# MAX31865_Layout_with_OLED.net
KiCad netlist of a schematic drawn in EAGLE
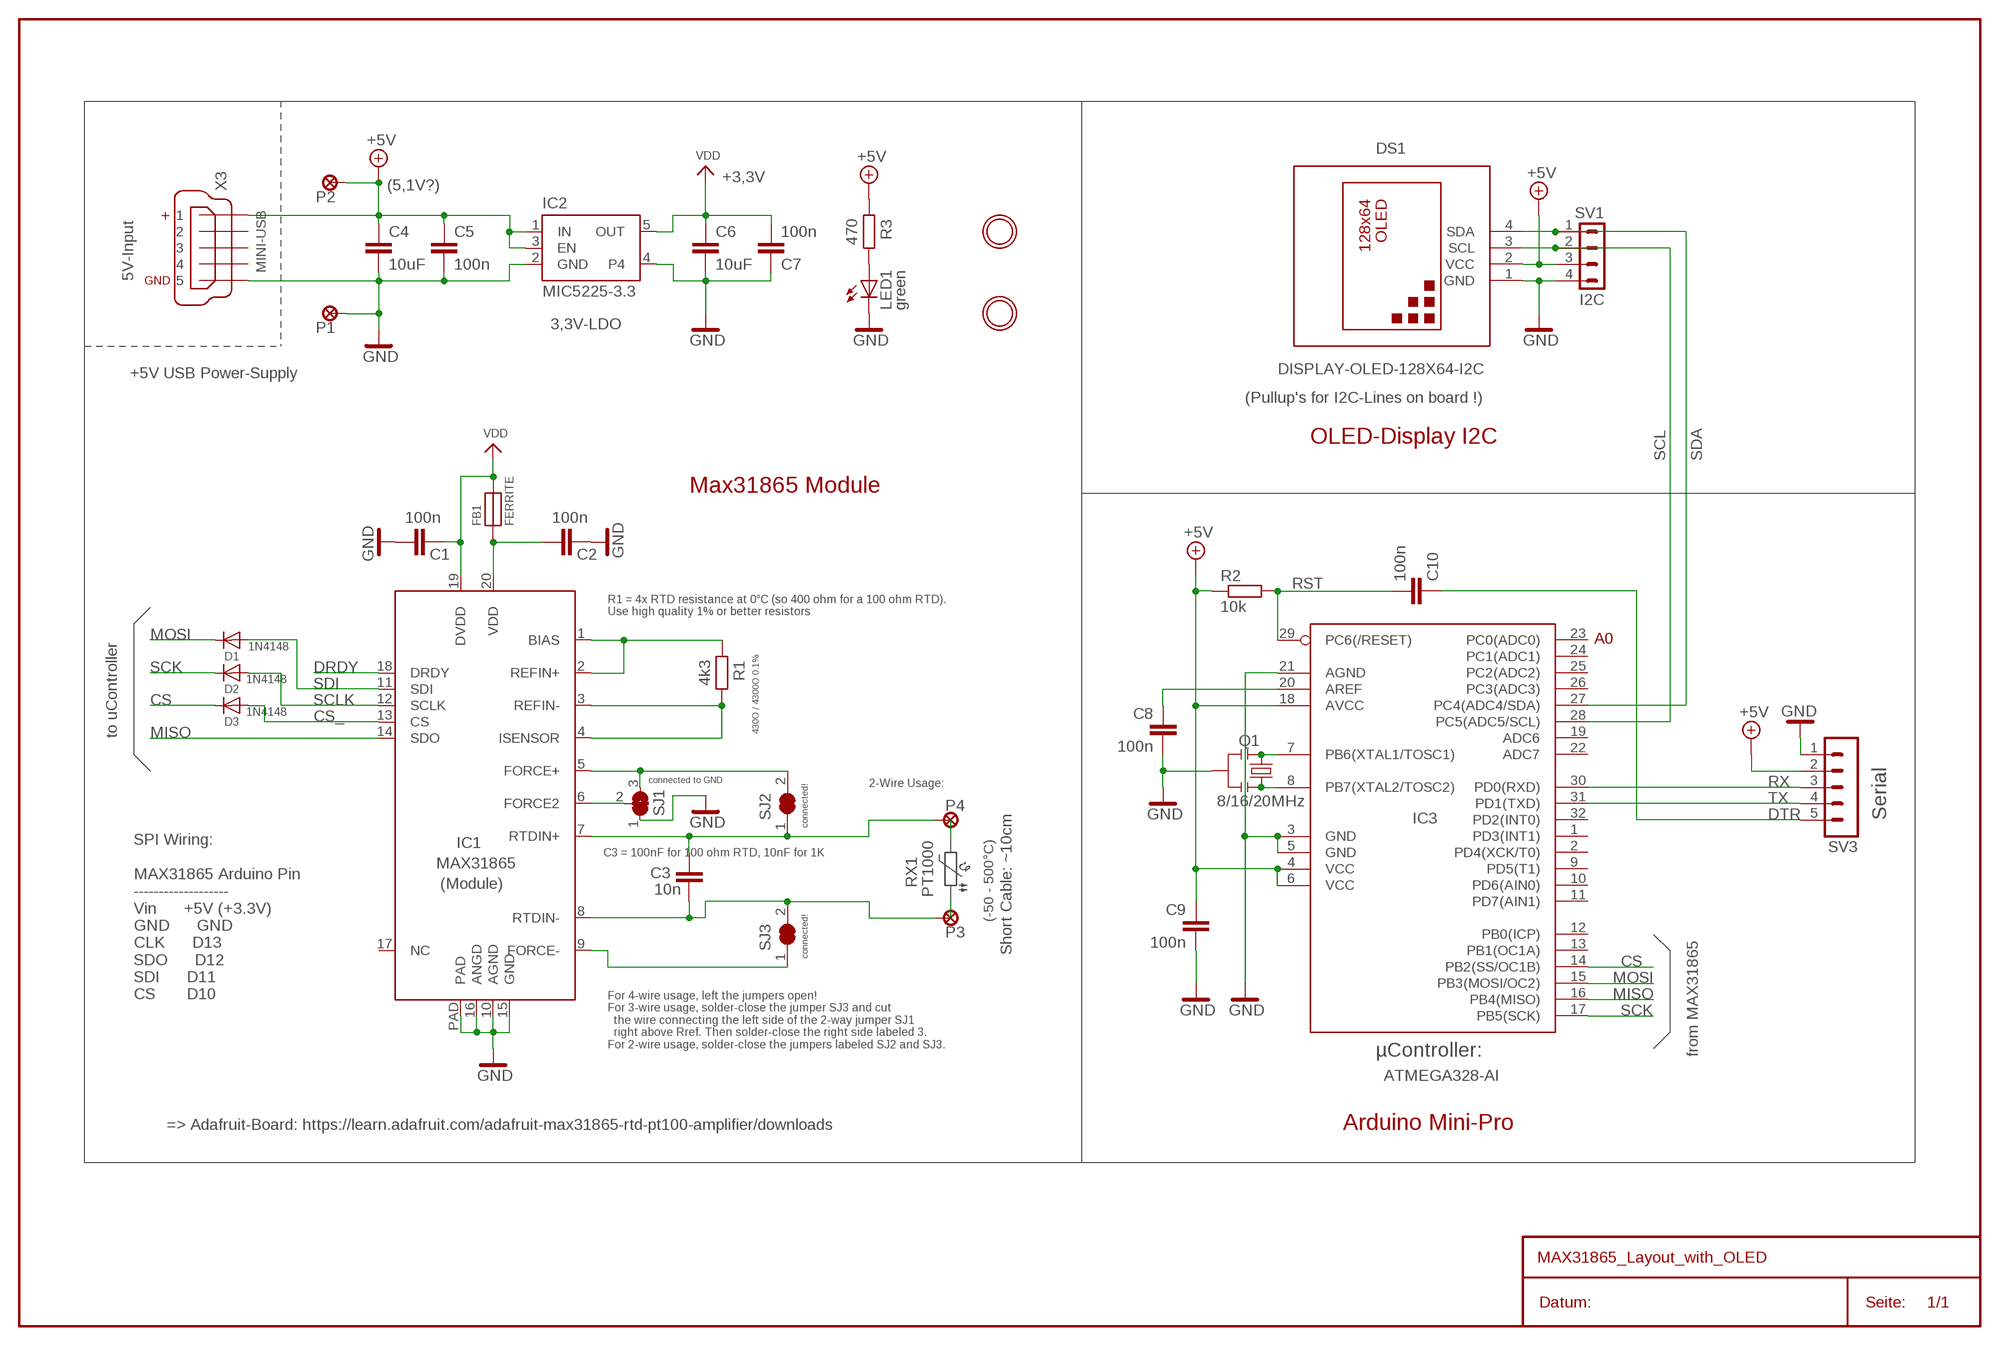
[diagram p0: schematic, sheet 1]

(export (version "E")
  (design (tool "Eeschema 10.0.6"))
  (components
    (comp (ref "C1")
      (value "100n")
      (footprint "eagle-import:C0603")
      (libsource (lib "eagle-import") (part "C-EUC0603"))
    )
    (comp (ref "C2")
      (value "100n")
      (footprint "eagle-import:C0603")
      (libsource (lib "eagle-import") (part "C-EUC0603"))
    )
    (comp (ref "C3")
      (value "10n")
      (footprint "eagle-import:C0603")
      (libsource (lib "eagle-import") (part "C-EUC0603"))
    )
    (comp (ref "C4")
      (value "10uF")
      (footprint "eagle-import:C0805")
      (libsource (lib "eagle-import") (part "C-EUC0805"))
    )
    (comp (ref "C5")
      (value "100n")
      (footprint "eagle-import:C0603")
      (libsource (lib "eagle-import") (part "C-EUC0603"))
    )
    (comp (ref "C6")
      (value "10uF")
      (footprint "eagle-import:C0603")
      (libsource (lib "eagle-import") (part "C-EUC0603"))
    )
    (comp (ref "C7")
      (value "100n")
      (footprint "eagle-import:C0603")
      (libsource (lib "eagle-import") (part "C-EUC0603"))
    )
    (comp (ref "C8")
      (value "100n")
      (footprint "eagle-import:C0603")
      (libsource (lib "eagle-import") (part "C-EUC0603"))
    )
    (comp (ref "C9")
      (value "100n")
      (footprint "eagle-import:C0603")
      (libsource (lib "eagle-import") (part "C-EUC0603"))
    )
    (comp (ref "C10")
      (value "100n")
      (footprint "eagle-import:C0603")
      (libsource (lib "eagle-import") (part "C-EUC0603"))
    )
    (comp (ref "D1")
      (value "1N4148")
      (footprint "eagle-import:SOD-323")
      (libsource (lib "eagle-import") (part "DIODESOD-323"))
    )
    (comp (ref "D2")
      (value "1N4148")
      (footprint "eagle-import:SOD-323")
      (libsource (lib "eagle-import") (part "DIODESOD-323"))
    )
    (comp (ref "D3")
      (value "1N4148")
      (footprint "eagle-import:SOD-323")
      (libsource (lib "eagle-import") (part "DIODESOD-323"))
    )
    (comp (ref "DS1")
      (value "DISPLAY-OLED-128X64-I2C")
      (footprint "eagle-import:DISPLAY-OLED-128X64-I2C")
      (libsource (lib "eagle-import") (part "DISPLAY-OLED-128X64-I2C"))
    )
    (comp (ref "FB1")
      (value "FERRITE")
      (footprint "eagle-import:0603")
      (libsource (lib "eagle-import") (part "FERRITE"))
    )
    (comp (ref "IC1")
      (value "MAX31865")
      (footprint "eagle-import:QFN20_4MM_0.65MM")
      (libsource (lib "eagle-import") (part "TEMP_MAX31865"))
    )
    (comp (ref "IC2")
      (value "MIC5225-3.3")
      (footprint "eagle-import:SOT23-5")
      (libsource (lib "eagle-import") (part "VREG_SOT23-5"))
    )
    (comp (ref "IC3")
      (value "ATMEGA328-AI")
      (footprint "eagle-import:TQFP32-08")
      (libsource (lib "eagle-import") (part "MEGA8-AI"))
    )
    (comp (ref "LED1")
      (value "green")
      (footprint "eagle-import:CHIPLED_0805")
      (libsource (lib "eagle-import") (part "LEDCHIPLED_0805"))
    )
    (comp (ref "P1")
      (value "LSP15")
      (footprint "eagle-import:LSP15")
      (libsource (lib "eagle-import") (part "LSP15"))
    )
    (comp (ref "P2")
      (value "LSP15")
      (footprint "eagle-import:LSP15")
      (libsource (lib "eagle-import") (part "LSP15"))
    )
    (comp (ref "P3")
      (value "LSP15")
      (footprint "eagle-import:LSP15")
      (libsource (lib "eagle-import") (part "LSP15"))
    )
    (comp (ref "P4")
      (value "LSP15")
      (footprint "eagle-import:LSP15")
      (libsource (lib "eagle-import") (part "LSP15"))
    )
    (comp (ref "Q1")
      (value "8/16/20MHz")
      (footprint "eagle-import:RESONATOR-SMD-1_1")
      (libsource (lib "eagle-import") (part "RESONATOR1{colon}1"))
    )
    (comp (ref "R1")
      (value "4k3")
      (footprint "eagle-import:R0603")
      (libsource (lib "eagle-import") (part "R-EU_R0603"))
    )
    (comp (ref "R2")
      (value "10k")
      (footprint "eagle-import:R0603")
      (libsource (lib "eagle-import") (part "R-EU_R0603"))
    )
    (comp (ref "R3")
      (value "470")
      (footprint "eagle-import:R0603")
      (libsource (lib "eagle-import") (part "R-EU_R0603"))
    )
    (comp (ref "SJ1")
      (value "SOLDERJUMPER_2WAY")
      (footprint "eagle-import:SOLDERJUMPER_2WAY_OPEN_NOPASTE")
      (libsource (lib "eagle-import") (part "SOLDERJUMPER_2WAY"))
    )
    (comp (ref "SJ2")
      (value "SOLDERJUMPER")
      (footprint "eagle-import:SOLDERJUMPER_ARROW_NOPASTE")
      (libsource (lib "eagle-import") (part "SOLDERJUMPER"))
    )
    (comp (ref "SJ3")
      (value "SOLDERJUMPER")
      (footprint "eagle-import:SOLDERJUMPER_ARROW_NOPASTE")
      (libsource (lib "eagle-import") (part "SOLDERJUMPER"))
    )
    (comp (ref "SV1")
      (value "I2C")
      (footprint "eagle-import:MA04-1")
      (libsource (lib "eagle-import") (part "MA04-10"))
    )
    (comp (ref "SV3")
      (value "MA05-1")
      (footprint "eagle-import:MA05-1")
      (libsource (lib "eagle-import") (part "MA05-1"))
    )
    (comp (ref "U$2")
      (value "MOUNTINGHOLE2.5")
      (footprint "eagle-import:MOUNTINGHOLE_2.5_PLATED")
      (libsource (lib "eagle-import") (part "MOUNTINGHOLE2.5"))
    )
    (comp (ref "U$19")
      (value "MOUNTINGHOLE2.5")
      (footprint "eagle-import:MOUNTINGHOLE_2.5_PLATED")
      (libsource (lib "eagle-import") (part "MOUNTINGHOLE2.5"))
    )
    (comp (ref "X3")
      (value "MINI-USB")
      (footprint "eagle-import:32005-201")
      (libsource (lib "eagle-import") (part "MINI-USB-32005-201"))
    )
  )
  (nets
    (net (code "1") (name "+5V") (class "Default")
      (node (ref "C4") (pin "1") (pinfunction "1_1") (pintype "passive"))
      (node (ref "C5") (pin "1") (pinfunction "1_1") (pintype "passive"))
      (node (ref "C9") (pin "1") (pinfunction "1_1") (pintype "passive"))
      (node (ref "DS1") (pin "2") (pinfunction "VCC_2") (pintype "power_in"))
      (node (ref "IC2") (pin "1") (pinfunction "IN_1") (pintype "power_in"))
      (node (ref "IC2") (pin "3") (pinfunction "EN_3") (pintype "input"))
      (node (ref "IC3") (pin "18") (pinfunction "AVCC_18") (pintype "bidirectional"))
      (node (ref "IC3") (pin "4") (pinfunction "VCC_4") (pintype "bidirectional"))
      (node (ref "IC3") (pin "6") (pinfunction "VCC_6") (pintype "bidirectional"))
      (node (ref "P2") (pin "P$1") (pinfunction "MP_P$1") (pintype "passive"))
      (node (ref "R2") (pin "1") (pinfunction "1_1") (pintype "passive"))
      (node (ref "R3") (pin "1") (pinfunction "1_1") (pintype "passive"))
      (node (ref "SV1") (pin "3") (pinfunction "3_3") (pintype "passive"))
      (node (ref "SV3") (pin "2") (pinfunction "2_2") (pintype "passive"))
      (node (ref "X3") (pin "1") (pinfunction "1_1") (pintype "passive"))
    )
    (net (code "2") (name "/CS") (class "Default")
      (node (ref "D3") (pin "C") (pinfunction "C_C") (pintype "passive"))
      (node (ref "IC3") (pin "14") (pinfunction "PB2(SS/OC1B)_14") (pintype "bidirectional"))
    )
    (net (code "3") (name "/CS_") (class "Default")
      (node (ref "D3") (pin "A") (pinfunction "A_A") (pintype "passive"))
      (node (ref "IC1") (pin "13") (pinfunction "CS_13") (pintype "input"))
    )
    (net (code "4") (name "/DRDY") (class "Default")
      (node (ref "IC1") (pin "18") (pinfunction "DRDY_18") (pintype "output"))
    )
    (net (code "5") (name "/DTR") (class "Default")
      (node (ref "C10") (pin "1") (pinfunction "1_1") (pintype "passive"))
      (node (ref "SV3") (pin "5") (pinfunction "5_5") (pintype "passive"))
    )
    (net (code "6") (name "/MISO") (class "Default")
      (node (ref "IC1") (pin "14") (pinfunction "SDO_14") (pintype "output"))
      (node (ref "IC3") (pin "16") (pinfunction "PB4(MISO)_16") (pintype "bidirectional"))
    )
    (net (code "7") (name "/MOSI") (class "Default")
      (node (ref "D1") (pin "C") (pinfunction "C_C") (pintype "passive"))
      (node (ref "IC3") (pin "15") (pinfunction "PB3(MOSI/OC2)_15") (pintype "bidirectional"))
    )
    (net (code "8") (name "/RST") (class "Default")
      (node (ref "C10") (pin "2") (pinfunction "2_2") (pintype "passive"))
      (node (ref "IC3") (pin "29") (pinfunction "PC6(/RESET)_29") (pintype "bidirectional"))
      (node (ref "R2") (pin "2") (pinfunction "2_2") (pintype "passive"))
    )
    (net (code "9") (name "/RX") (class "Default")
      (node (ref "IC3") (pin "30") (pinfunction "PD0(RXD)_30") (pintype "bidirectional"))
      (node (ref "SV3") (pin "3") (pinfunction "3_3") (pintype "passive"))
    )
    (net (code "10") (name "/SCK") (class "Default")
      (node (ref "D2") (pin "C") (pinfunction "C_C") (pintype "passive"))
      (node (ref "IC3") (pin "17") (pinfunction "PB5(SCK)_17") (pintype "bidirectional"))
    )
    (net (code "11") (name "/SCL") (class "Default")
      (node (ref "DS1") (pin "3") (pinfunction "SCL_3") (pintype "bidirectional"))
      (node (ref "IC3") (pin "28") (pinfunction "PC5(ADC5/SCL)_28") (pintype "bidirectional"))
      (node (ref "SV1") (pin "2") (pinfunction "2_2") (pintype "passive"))
    )
    (net (code "12") (name "/SCLK") (class "Default")
      (node (ref "D2") (pin "A") (pinfunction "A_A") (pintype "passive"))
      (node (ref "IC1") (pin "12") (pinfunction "SCLK_12") (pintype "input"))
    )
    (net (code "13") (name "/SDA") (class "Default")
      (node (ref "DS1") (pin "4") (pinfunction "SDA_4") (pintype "bidirectional"))
      (node (ref "IC3") (pin "27") (pinfunction "PC4(ADC4/SDA)_27") (pintype "bidirectional"))
      (node (ref "SV1") (pin "1") (pinfunction "1_1") (pintype "passive"))
    )
    (net (code "14") (name "/SDI") (class "Default")
      (node (ref "D1") (pin "A") (pinfunction "A_A") (pintype "passive"))
      (node (ref "IC1") (pin "11") (pinfunction "SDI_11") (pintype "input"))
    )
    (net (code "15") (name "/TX") (class "Default")
      (node (ref "IC3") (pin "31") (pinfunction "PD1(TXD)_31") (pintype "bidirectional"))
      (node (ref "SV3") (pin "4") (pinfunction "4_4") (pintype "passive"))
    )
    (net (code "16") (name "GND") (class "Default")
      (node (ref "C1") (pin "2") (pinfunction "2_2") (pintype "passive"))
      (node (ref "C2") (pin "1") (pinfunction "1_1") (pintype "passive"))
      (node (ref "C4") (pin "2") (pinfunction "2_2") (pintype "passive"))
      (node (ref "C5") (pin "2") (pinfunction "2_2") (pintype "passive"))
      (node (ref "C6") (pin "2") (pinfunction "2_2") (pintype "passive"))
      (node (ref "C7") (pin "1") (pinfunction "1_1") (pintype "passive"))
      (node (ref "C8") (pin "2") (pinfunction "2_2") (pintype "passive"))
      (node (ref "C9") (pin "2") (pinfunction "2_2") (pintype "passive"))
      (node (ref "DS1") (pin "1") (pinfunction "GND_1") (pintype "power_in"))
      (node (ref "IC1") (pin "10") (pinfunction "AGND_10") (pintype "power_in"))
      (node (ref "IC1") (pin "15") (pinfunction "GND_15") (pintype "power_in"))
      (node (ref "IC1") (pin "16") (pinfunction "ANGD_16") (pintype "power_in"))
      (node (ref "IC1") (pin "PAD") (pinfunction "PAD_PAD") (pintype "power_in"))
      (node (ref "IC2") (pin "2") (pinfunction "GND_2") (pintype "power_in"))
      (node (ref "IC2") (pin "4") (pinfunction "P4_4") (pintype "bidirectional"))
      (node (ref "IC3") (pin "21") (pinfunction "AGND_21") (pintype "bidirectional"))
      (node (ref "IC3") (pin "3") (pinfunction "GND_3") (pintype "bidirectional"))
      (node (ref "IC3") (pin "5") (pinfunction "GND_5") (pintype "bidirectional"))
      (node (ref "LED1") (pin "C") (pinfunction "C_C") (pintype "passive"))
      (node (ref "P1") (pin "P$1") (pinfunction "MP_P$1") (pintype "passive"))
      (node (ref "Q1") (pin "2") (pinfunction "2_2") (pintype "passive"))
      (node (ref "SJ1") (pin "1") (pinfunction "1_1") (pintype "passive"))
      (node (ref "SV1") (pin "4") (pinfunction "4_4") (pintype "passive"))
      (node (ref "SV3") (pin "1") (pinfunction "1_1") (pintype "passive"))
      (node (ref "X3") (pin "5") (pinfunction "5_5") (pintype "passive"))
    )
    (net (code "17") (name "Net-(FB1-P$1)") (class "Default")
      (node (ref "C2") (pin "2") (pinfunction "2_2") (pintype "passive"))
      (node (ref "FB1") (pin "1") (pinfunction "P$1_1") (pintype "bidirectional"))
      (node (ref "IC1") (pin "20") (pinfunction "VDD_20") (pintype "power_in"))
    )
    (net (code "18") (name "Net-(IC1-BIAS)") (class "Default")
      (node (ref "IC1") (pin "1") (pinfunction "BIAS_1") (pintype "output"))
      (node (ref "IC1") (pin "2") (pinfunction "REFIN+_2") (pintype "bidirectional"))
      (node (ref "R1") (pin "1") (pinfunction "1_1") (pintype "passive"))
    )
    (net (code "19") (name "Net-(IC1-FORCE+)") (class "Default")
      (node (ref "IC1") (pin "5") (pinfunction "FORCE+_5") (pintype "output"))
      (node (ref "SJ1") (pin "3") (pinfunction "3_3") (pintype "passive"))
      (node (ref "SJ2") (pin "2") (pinfunction "2_2") (pintype "passive"))
    )
    (net (code "20") (name "Net-(IC1-FORCE-)") (class "Default")
      (node (ref "IC1") (pin "9") (pinfunction "FORCE-_9") (pintype "input"))
      (node (ref "SJ3") (pin "1") (pinfunction "1_1") (pintype "passive"))
    )
    (net (code "21") (name "Net-(IC1-FORCE2)") (class "Default")
      (node (ref "IC1") (pin "6") (pinfunction "FORCE2_6") (pintype "bidirectional"))
      (node (ref "SJ1") (pin "2") (pinfunction "2_2") (pintype "passive"))
    )
    (net (code "22") (name "Net-(IC1-ISENSOR)") (class "Default")
      (node (ref "IC1") (pin "3") (pinfunction "REFIN-_3") (pintype "bidirectional"))
      (node (ref "IC1") (pin "4") (pinfunction "ISENSOR_4") (pintype "input"))
      (node (ref "R1") (pin "2") (pinfunction "2_2") (pintype "passive"))
    )
    (net (code "23") (name "Net-(IC1-RTDIN+)") (class "Default")
      (node (ref "C3") (pin "1") (pinfunction "1_1") (pintype "passive"))
      (node (ref "IC1") (pin "7") (pinfunction "RTDIN+_7") (pintype "bidirectional"))
      (node (ref "P4") (pin "P$1") (pinfunction "MP_P$1") (pintype "passive"))
      (node (ref "SJ2") (pin "1") (pinfunction "1_1") (pintype "passive"))
    )
    (net (code "24") (name "Net-(IC1-RTDIN-)") (class "Default")
      (node (ref "C3") (pin "2") (pinfunction "2_2") (pintype "passive"))
      (node (ref "IC1") (pin "8") (pinfunction "RTDIN-_8") (pintype "bidirectional"))
      (node (ref "P3") (pin "P$1") (pinfunction "MP_P$1") (pintype "passive"))
      (node (ref "SJ3") (pin "2") (pinfunction "2_2") (pintype "passive"))
    )
    (net (code "25") (name "Net-(IC3-AREF)") (class "Default")
      (node (ref "C8") (pin "1") (pinfunction "1_1") (pintype "passive"))
      (node (ref "IC3") (pin "20") (pinfunction "AREF_20") (pintype "bidirectional"))
    )
    (net (code "26") (name "Net-(IC3-PB6(XTAL1{slash}TOSC1))") (class "Default")
      (node (ref "IC3") (pin "7") (pinfunction "PB6(XTAL1/TOSC1)_7") (pintype "bidirectional"))
      (node (ref "Q1") (pin "1") (pinfunction "1_1") (pintype "passive"))
    )
    (net (code "27") (name "Net-(IC3-PB7(XTAL2{slash}TOSC2))") (class "Default")
      (node (ref "IC3") (pin "8") (pinfunction "PB7(XTAL2/TOSC2)_8") (pintype "bidirectional"))
      (node (ref "Q1") (pin "3") (pinfunction "3_3") (pintype "passive"))
    )
    (net (code "28") (name "Net-(LED1-PadA)") (class "Default")
      (node (ref "LED1") (pin "A") (pinfunction "A_A") (pintype "passive"))
      (node (ref "R3") (pin "2") (pinfunction "2_2") (pintype "passive"))
    )
    (net (code "29") (name "VDD") (class "Default")
      (node (ref "C1") (pin "1") (pinfunction "1_1") (pintype "passive"))
      (node (ref "C6") (pin "1") (pinfunction "1_1") (pintype "passive"))
      (node (ref "C7") (pin "2") (pinfunction "2_2") (pintype "passive"))
      (node (ref "FB1") (pin "2") (pinfunction "P$2_2") (pintype "bidirectional"))
      (node (ref "IC1") (pin "19") (pinfunction "DVDD_19") (pintype "power_in"))
      (node (ref "IC2") (pin "5") (pinfunction "OUT_5") (pintype "power_in"))
    )
    (net (code "30") (name "unconnected-(IC1-NC-Pad17)") (class "Default")
      (node (ref "IC1") (pin "17") (pinfunction "NC_17") (pintype "no_connect"))
    )
    (net (code "31") (name "unconnected-(IC3-ADC6-Pad19)") (class "Default")
      (node (ref "IC3") (pin "19") (pinfunction "ADC6_19") (pintype "bidirectional"))
    )
    (net (code "32") (name "unconnected-(IC3-ADC7-Pad22)") (class "Default")
      (node (ref "IC3") (pin "22") (pinfunction "ADC7_22") (pintype "bidirectional"))
    )
    (net (code "33") (name "unconnected-(IC3-PB0(ICP)-Pad12)") (class "Default")
      (node (ref "IC3") (pin "12") (pinfunction "PB0(ICP)_12") (pintype "bidirectional"))
    )
    (net (code "34") (name "unconnected-(IC3-PB1(OC1A)-Pad13)") (class "Default")
      (node (ref "IC3") (pin "13") (pinfunction "PB1(OC1A)_13") (pintype "bidirectional"))
    )
    (net (code "35") (name "unconnected-(IC3-PC0(ADC0)-Pad23)") (class "Default")
      (node (ref "IC3") (pin "23") (pinfunction "PC0(ADC0)_23") (pintype "bidirectional"))
    )
    (net (code "36") (name "unconnected-(IC3-PC1(ADC1)-Pad24)") (class "Default")
      (node (ref "IC3") (pin "24") (pinfunction "PC1(ADC1)_24") (pintype "bidirectional"))
    )
    (net (code "37") (name "unconnected-(IC3-PC2(ADC2)-Pad25)") (class "Default")
      (node (ref "IC3") (pin "25") (pinfunction "PC2(ADC2)_25") (pintype "bidirectional"))
    )
    (net (code "38") (name "unconnected-(IC3-PC3(ADC3)-Pad26)") (class "Default")
      (node (ref "IC3") (pin "26") (pinfunction "PC3(ADC3)_26") (pintype "bidirectional"))
    )
    (net (code "39") (name "unconnected-(IC3-PD2(INT0)-Pad32)") (class "Default")
      (node (ref "IC3") (pin "32") (pinfunction "PD2(INT0)_32") (pintype "bidirectional"))
    )
    (net (code "40") (name "unconnected-(IC3-PD3(INT1)-Pad1)") (class "Default")
      (node (ref "IC3") (pin "1") (pinfunction "PD3(INT1)_1") (pintype "bidirectional"))
    )
    (net (code "41") (name "unconnected-(IC3-PD4(XCK{slash}T0)-Pad2)") (class "Default")
      (node (ref "IC3") (pin "2") (pinfunction "PD4(XCK/T0)_2") (pintype "bidirectional"))
    )
    (net (code "42") (name "unconnected-(IC3-PD5(T1)-Pad9)") (class "Default")
      (node (ref "IC3") (pin "9") (pinfunction "PD5(T1)_9") (pintype "bidirectional"))
    )
    (net (code "43") (name "unconnected-(IC3-PD6(AIN0)-Pad10)") (class "Default")
      (node (ref "IC3") (pin "10") (pinfunction "PD6(AIN0)_10") (pintype "bidirectional"))
    )
    (net (code "44") (name "unconnected-(IC3-PD7(AIN1)-Pad11)") (class "Default")
      (node (ref "IC3") (pin "11") (pinfunction "PD7(AIN1)_11") (pintype "bidirectional"))
    )
    (net (code "45") (name "unconnected-(X3-Pad2)") (class "Default")
      (node (ref "X3") (pin "2") (pinfunction "2_2") (pintype "passive"))
    )
    (net (code "46") (name "unconnected-(X3-Pad3)") (class "Default")
      (node (ref "X3") (pin "3") (pinfunction "3_3") (pintype "passive"))
    )
    (net (code "47") (name "unconnected-(X3-Pad4)") (class "Default")
      (node (ref "X3") (pin "4") (pinfunction "4_4") (pintype "passive"))
    )
  )
)
